# lab2_task1.net
KiCad netlist of a schematic drawn in EAGLE
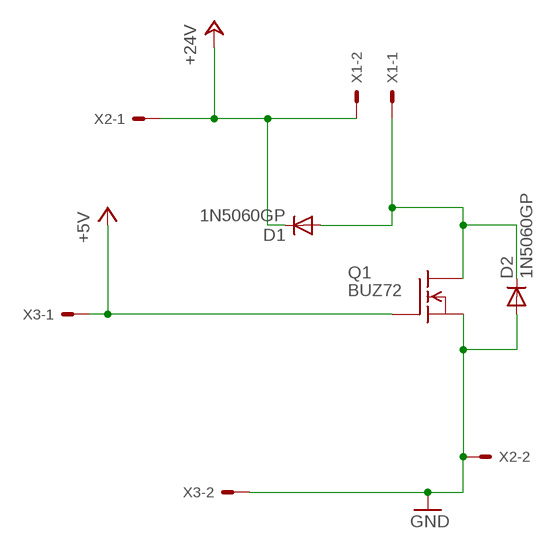
[diagram p0: schematic, sheet 1]

(export (version "E")
  (design (tool "Eeschema 10.0.6"))
  (components
    (comp (ref "D1")
      (value "1N5060GP")
      (footprint "eagle-import:DO15-12")
      (libsource (lib "eagle-import") (part "1N5060GP"))
    )
    (comp (ref "D2")
      (value "1N5060GP")
      (footprint "eagle-import:DO15-12")
      (libsource (lib "eagle-import") (part "1N5060GP"))
    )
    (comp (ref "Q1")
      (value "BUZ72")
      (footprint "eagle-import:TO220")
      (libsource (lib "eagle-import") (part "BUZ72"))
    )
    (comp (ref "X1")
      (value "KK-156-2")
      (footprint "eagle-import:KK-156-2")
      (libsource (lib "eagle-import") (part "KK-156-2"))
    )
    (comp (ref "X2")
      (value "KK-156-2")
      (footprint "eagle-import:KK-156-2")
      (libsource (lib "eagle-import") (part "KK-156-2"))
    )
    (comp (ref "X3")
      (value "KK-156-2")
      (footprint "eagle-import:KK-156-2")
      (libsource (lib "eagle-import") (part "KK-156-2"))
    )
  )
  (nets
    (net (code "1") (name "+5V") (class "Default")
      (node (ref "Q1") (pin "1") (pinfunction "G_1") (pintype "passive"))
      (node (ref "X3") (pin "1") (pinfunction "S_1") (pintype "passive"))
    )
    (net (code "2") (name "+24V") (class "Default")
      (node (ref "D1") (pin "C") (pinfunction "C_C") (pintype "passive"))
      (node (ref "X1") (pin "2") (pinfunction "S_2") (pintype "passive"))
      (node (ref "X2") (pin "1") (pinfunction "S_1") (pintype "passive"))
    )
    (net (code "3") (name "GND") (class "Default")
      (node (ref "D2") (pin "A") (pinfunction "A_A") (pintype "passive"))
      (node (ref "Q1") (pin "3") (pinfunction "S_3") (pintype "passive"))
      (node (ref "X2") (pin "2") (pinfunction "S_2") (pintype "passive"))
      (node (ref "X3") (pin "2") (pinfunction "S_2") (pintype "passive"))
    )
    (net (code "4") (name "Net-(Q1-D)") (class "Default")
      (node (ref "D1") (pin "A") (pinfunction "A_A") (pintype "passive"))
      (node (ref "D2") (pin "C") (pinfunction "C_C") (pintype "passive"))
      (node (ref "Q1") (pin "2") (pinfunction "D_2") (pintype "passive"))
      (node (ref "X1") (pin "1") (pinfunction "S_1") (pintype "passive"))
    )
  )
)
